# bleumaus-nrf51822-mk-1_0_3.net
KiCad netlist of a schematic drawn in EAGLE
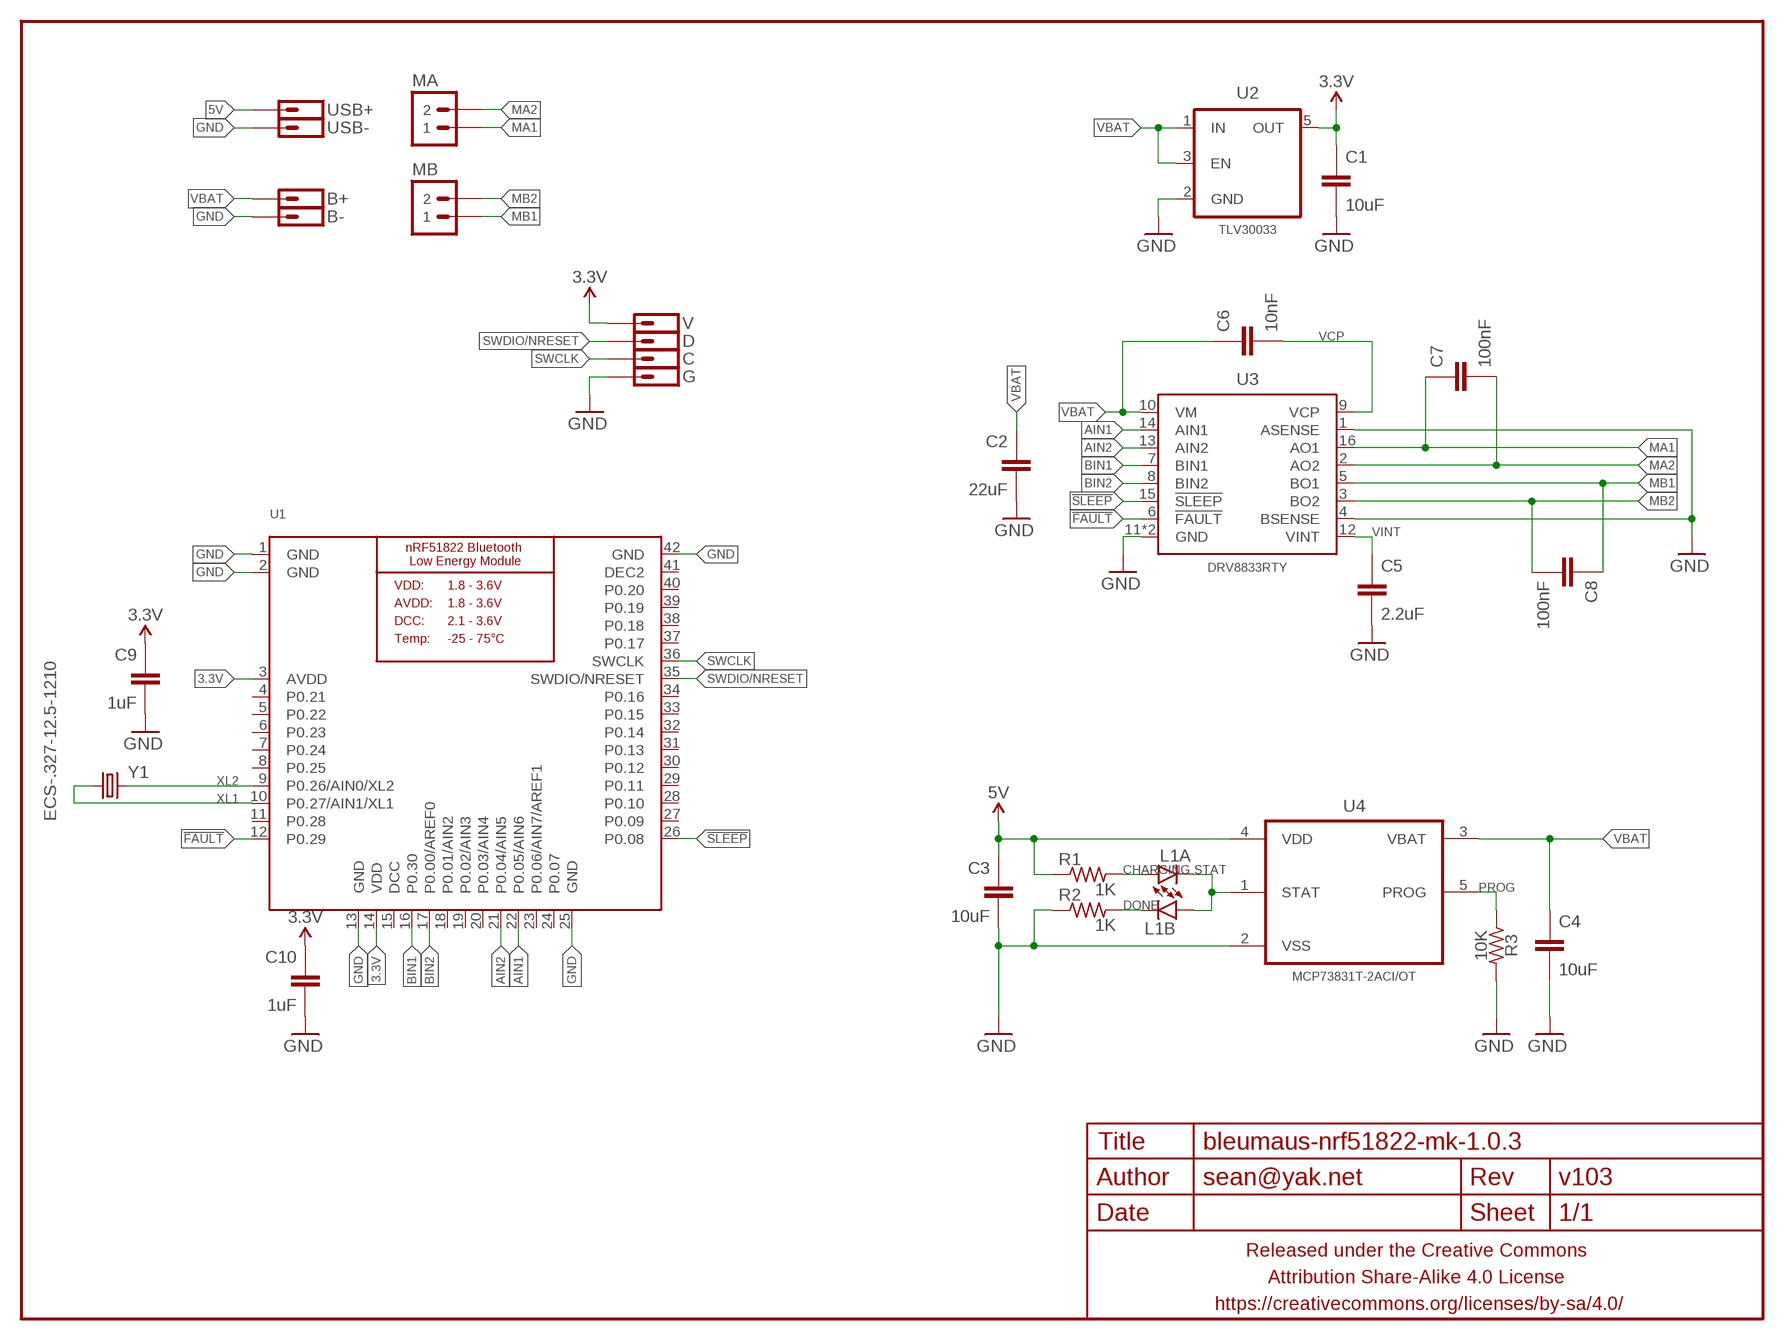
[diagram p0: schematic, sheet 1]

(export (version "E")
  (design (tool "Eeschema 10.0.6"))
  (components
    (comp (ref "B+")
      (value "M01SMD-1DIA")
      (footprint "eagle-import:1X01-SMD-1MM-DIA")
      (libsource (lib "eagle-import") (part "M01SMD-1DIA"))
    )
    (comp (ref "B-")
      (value "M01SMD-1DIA")
      (footprint "eagle-import:1X01-SMD-1MM-DIA")
      (libsource (lib "eagle-import") (part "M01SMD-1DIA"))
    )
    (comp (ref "C")
      (value "M01SMD-1DIA")
      (footprint "eagle-import:1X01-SMD-1MM-DIA")
      (libsource (lib "eagle-import") (part "M01SMD-1DIA"))
    )
    (comp (ref "C1")
      (value "10uF")
      (footprint "eagle-import:C0402")
      (libsource (lib "eagle-import") (part "CAPACITOR-CERAMICC0402"))
    )
    (comp (ref "C2")
      (value "22uF")
      (footprint "eagle-import:C1206")
      (libsource (lib "eagle-import") (part "CAPACITOR-CERAMICC1206"))
    )
    (comp (ref "C3")
      (value "10uF")
      (footprint "eagle-import:C0402")
      (libsource (lib "eagle-import") (part "CAPACITOR-CERAMICC0402"))
    )
    (comp (ref "C4")
      (value "10uF")
      (footprint "eagle-import:C0402")
      (libsource (lib "eagle-import") (part "CAPACITOR-CERAMICC0402"))
    )
    (comp (ref "C5")
      (value "2.2uF")
      (footprint "eagle-import:C0402")
      (libsource (lib "eagle-import") (part "CAPACITOR-CERAMICC0402"))
    )
    (comp (ref "C6")
      (value "10nF")
      (footprint "eagle-import:C0402")
      (libsource (lib "eagle-import") (part "CAPACITOR-CERAMICC0402"))
    )
    (comp (ref "C7")
      (value "100nF")
      (footprint "eagle-import:C0402")
      (libsource (lib "eagle-import") (part "CAPACITOR-CERAMICC0402"))
    )
    (comp (ref "C8")
      (value "100nF")
      (footprint "eagle-import:C0402")
      (libsource (lib "eagle-import") (part "CAPACITOR-CERAMICC0402"))
    )
    (comp (ref "C9")
      (value "1uF")
      (footprint "eagle-import:C0402")
      (libsource (lib "eagle-import") (part "CAPACITOR-CERAMICC0402"))
    )
    (comp (ref "C10")
      (value "1uF")
      (footprint "eagle-import:C0402")
      (libsource (lib "eagle-import") (part "CAPACITOR-CERAMICC0402"))
    )
    (comp (ref "D")
      (value "M01SMD-1DIA")
      (footprint "eagle-import:1X01-SMD-1MM-DIA")
      (libsource (lib "eagle-import") (part "M01SMD-1DIA"))
    )
    (comp (ref "FRAME1")
      (value "FRAME-LETTERNO_PACKAGE")
      (footprint "eagle-import:DUMMY")
      (fields
        (field (name "DESIGNER") "sean@yak.net")
        (field (name "VERSION") "v103")
        (field (name "DESIGNER_1") "sean@yak.net")
        (field (name "VERSION_1") "v103")
      )
      (libsource (lib "eagle-import") (part "FRAME-LETTERNO_PACKAGE"))
    )
    (comp (ref "G")
      (value "M01SMD-1DIA")
      (footprint "eagle-import:1X01-SMD-1MM-DIA")
      (libsource (lib "eagle-import") (part "M01SMD-1DIA"))
    )
    (comp (ref "L1")
      (value "LED-BICOLORSML-P24MUW")
      (footprint "eagle-import:SML-P24MUW")
      (libsource (lib "eagle-import") (part "LED-BICOLORSML-P24MUW"))
    )
    (comp (ref "MA")
      (value "M02PTH-2MM")
      (footprint "eagle-import:1X02-2MM-PTH")
      (libsource (lib "eagle-import") (part "M02PTH-2MM"))
    )
    (comp (ref "MB")
      (value "M02PTH-2MM")
      (footprint "eagle-import:1X02-2MM-PTH")
      (libsource (lib "eagle-import") (part "M02PTH-2MM"))
    )
    (comp (ref "R1")
      (value "1K")
      (footprint "eagle-import:R0402")
      (libsource (lib "eagle-import") (part "RESISTORR0402"))
    )
    (comp (ref "R2")
      (value "1K")
      (footprint "eagle-import:R0402")
      (libsource (lib "eagle-import") (part "RESISTORR0402"))
    )
    (comp (ref "R3")
      (value "10K")
      (footprint "eagle-import:R0402")
      (libsource (lib "eagle-import") (part "RESISTORR0402"))
    )
    (comp (ref "U1")
      (value "NRF51822_MODULE_MDBT40")
      (footprint "eagle-import:BLE_MODULE_RAYTAC_MDBT40")
      (libsource (lib "eagle-import") (part "NRF51822_MODULE_MDBT40"))
    )
    (comp (ref "U2")
      (value "TLV30033")
      (footprint "eagle-import:SC70-TIGHTER")
      (libsource (lib "eagle-import") (part "V_REG_ENTLV700XXDCK-TIGHTER"))
    )
    (comp (ref "U3")
      (value "DRV8833RTY")
      (footprint "eagle-import:PWQFN-16")
      (libsource (lib "eagle-import") (part "DRV8833RTY"))
    )
    (comp (ref "U4")
      (value "MCP73831T-2ACI/OT")
      (footprint "eagle-import:SOT95P280X145-5N")
      (libsource (lib "eagle-import") (part "MCP73831T-2ACI/OT"))
    )
    (comp (ref "USB+")
      (value "M01SMD-1DIA")
      (footprint "eagle-import:1X01-SMD-1MM-DIA")
      (libsource (lib "eagle-import") (part "M01SMD-1DIA"))
    )
    (comp (ref "USB-")
      (value "M01SMD-1DIA")
      (footprint "eagle-import:1X01-SMD-1MM-DIA")
      (libsource (lib "eagle-import") (part "M01SMD-1DIA"))
    )
    (comp (ref "V")
      (value "M01SMD-1DIA")
      (footprint "eagle-import:1X01-SMD-1MM-DIA")
      (libsource (lib "eagle-import") (part "M01SMD-1DIA"))
    )
    (comp (ref "Y1")
      (value "ECS-.327-12.5-1210")
      (footprint "eagle-import:CRYSTAL-1X1.2MM")
      (libsource (lib "eagle-import") (part "CRYSTAL1X1.2MM"))
    )
  )
  (nets
    (net (code "1") (name "/CHARGING") (class "Default")
      (node (ref "L1") (pin "1") (pinfunction "A_1") (pintype "passive"))
      (node (ref "R1") (pin "2") (pinfunction "2_2") (pintype "passive"))
    )
    (net (code "2") (name "/DCC") (class "Default")
      (node (ref "U1") (pin "15") (pinfunction "DCC_15") (pintype "power_in"))
    )
    (net (code "3") (name "/DEC2") (class "Default")
      (node (ref "U1") (pin "41") (pinfunction "DEC2_41") (pintype "power_in"))
    )
    (net (code "4") (name "/DONE") (class "Default")
      (node (ref "L1") (pin "3") (pinfunction "C_3") (pintype "passive"))
      (node (ref "R2") (pin "2") (pinfunction "2_2") (pintype "passive"))
    )
    (net (code "5") (name "/PROG") (class "Default")
      (node (ref "R3") (pin "1") (pinfunction "1_1") (pintype "passive"))
      (node (ref "U4") (pin "5") (pinfunction "PROG_5") (pintype "input"))
    )
    (net (code "6") (name "/STAT") (class "Default")
      (node (ref "L1") (pin "2") (pinfunction "A_2") (pintype "passive"))
      (node (ref "L1") (pin "4") (pinfunction "C_4") (pintype "passive"))
      (node (ref "U4") (pin "1") (pinfunction "STAT_1") (pintype "output"))
    )
    (net (code "7") (name "/VCP") (class "Default")
      (node (ref "C6") (pin "2") (pinfunction "2_2") (pintype "passive"))
      (node (ref "U3") (pin "9") (pinfunction "VCP_9") (pintype "bidirectional"))
    )
    (net (code "8") (name "/VINT") (class "Default")
      (node (ref "C5") (pin "1") (pinfunction "1_1") (pintype "passive"))
      (node (ref "U3") (pin "12") (pinfunction "VINT_12") (pintype "bidirectional"))
    )
    (net (code "9") (name "/XL1") (class "Default")
      (node (ref "U1") (pin "10") (pinfunction "P0.27/AIN1/XL1_10") (pintype "bidirectional"))
      (node (ref "Y1") (pin "1") (pinfunction "1_1") (pintype "passive"))
    )
    (net (code "10") (name "/XL2") (class "Default")
      (node (ref "U1") (pin "9") (pinfunction "P0.26/AIN0/XL2_9") (pintype "bidirectional"))
      (node (ref "Y1") (pin "2") (pinfunction "2_2") (pintype "passive"))
    )
    (net (code "11") (name "/~{FAULT}") (class "Default")
      (node (ref "U1") (pin "12") (pinfunction "P0.29_12") (pintype "bidirectional"))
      (node (ref "U3") (pin "6") (pinfunction "~{FAULT}_6") (pintype "output"))
    )
    (net (code "12") (name "/~{SLEEP}") (class "Default")
      (node (ref "U1") (pin "26") (pinfunction "P0.08_26") (pintype "bidirectional"))
      (node (ref "U3") (pin "15") (pinfunction "~{SLEEP}_15") (pintype "input"))
    )
    (net (code "13") (name "3.3V") (class "Default")
      (node (ref "C1") (pin "1") (pinfunction "1_1") (pintype "passive"))
      (node (ref "C10") (pin "1") (pinfunction "1_1") (pintype "passive"))
      (node (ref "C9") (pin "1") (pinfunction "1_1") (pintype "passive"))
      (node (ref "U1") (pin "14") (pinfunction "VDD_14") (pintype "power_in"))
      (node (ref "U1") (pin "3") (pinfunction "AVDD_3") (pintype "power_in"))
      (node (ref "U2") (pin "5") (pinfunction "OUT_5") (pintype "passive"))
      (node (ref "V") (pin "P$1") (pinfunction "1_P$1") (pintype "passive"))
    )
    (net (code "14") (name "5V") (class "Default")
      (node (ref "C3") (pin "1") (pinfunction "1_1") (pintype "passive"))
      (node (ref "R1") (pin "1") (pinfunction "1_1") (pintype "passive"))
      (node (ref "U4") (pin "4") (pinfunction "VDD_4") (pintype "power_in"))
      (node (ref "USB+") (pin "P$1") (pinfunction "1_P$1") (pintype "passive"))
    )
    (net (code "15") (name "AIN1") (class "Default")
      (node (ref "U1") (pin "22") (pinfunction "P0.05/AIN6_22") (pintype "bidirectional"))
      (node (ref "U3") (pin "14") (pinfunction "AIN1_14") (pintype "input"))
    )
    (net (code "16") (name "AIN2") (class "Default")
      (node (ref "U1") (pin "21") (pinfunction "P0.04/AIN5_21") (pintype "bidirectional"))
      (node (ref "U3") (pin "13") (pinfunction "AIN2_13") (pintype "input"))
    )
    (net (code "17") (name "BIN1") (class "Default")
      (node (ref "U1") (pin "16") (pinfunction "P0.30_16") (pintype "bidirectional"))
      (node (ref "U3") (pin "7") (pinfunction "BIN1_7") (pintype "input"))
    )
    (net (code "18") (name "BIN2") (class "Default")
      (node (ref "U1") (pin "17") (pinfunction "P0.00/AREF0_17") (pintype "bidirectional"))
      (node (ref "U3") (pin "8") (pinfunction "BIN2_8") (pintype "input"))
    )
    (net (code "19") (name "GND") (class "Default")
      (node (ref "B-") (pin "P$1") (pinfunction "1_P$1") (pintype "passive"))
      (node (ref "C1") (pin "2") (pinfunction "2_2") (pintype "passive"))
      (node (ref "C10") (pin "2") (pinfunction "2_2") (pintype "passive"))
      (node (ref "C2") (pin "2") (pinfunction "2_2") (pintype "passive"))
      (node (ref "C3") (pin "2") (pinfunction "2_2") (pintype "passive"))
      (node (ref "C4") (pin "2") (pinfunction "2_2") (pintype "passive"))
      (node (ref "C5") (pin "2") (pinfunction "2_2") (pintype "passive"))
      (node (ref "C9") (pin "2") (pinfunction "2_2") (pintype "passive"))
      (node (ref "G") (pin "P$1") (pinfunction "1_P$1") (pintype "passive"))
      (node (ref "R2") (pin "1") (pinfunction "1_1") (pintype "passive"))
      (node (ref "R3") (pin "2") (pinfunction "2_2") (pintype "passive"))
      (node (ref "U1") (pin "1") (pinfunction "GND_1") (pintype "power_in"))
      (node (ref "U1") (pin "13") (pinfunction "GND_13") (pintype "power_in"))
      (node (ref "U1") (pin "2") (pinfunction "GND_2") (pintype "power_in"))
      (node (ref "U1") (pin "25") (pinfunction "GND_25") (pintype "power_in"))
      (node (ref "U1") (pin "42") (pinfunction "GND_42") (pintype "power_in"))
      (node (ref "U2") (pin "2") (pinfunction "GND_2") (pintype "input"))
      (node (ref "U3") (pin "1") (pinfunction "ASENSE_1") (pintype "bidirectional"))
      (node (ref "U3") (pin "11") (pinfunction "GND_11") (pintype "bidirectional"))
      (node (ref "U3") (pin "17") (pinfunction "GND_17") (pintype "bidirectional"))
      (node (ref "U3") (pin "4") (pinfunction "BSENSE_4") (pintype "bidirectional"))
      (node (ref "U4") (pin "2") (pinfunction "VSS_2") (pintype "power_in"))
      (node (ref "USB-") (pin "P$1") (pinfunction "1_P$1") (pintype "passive"))
    )
    (net (code "20") (name "MA1") (class "Default")
      (node (ref "C7") (pin "1") (pinfunction "1_1") (pintype "passive"))
      (node (ref "MA") (pin "P$1") (pinfunction "1_P$1") (pintype "passive"))
      (node (ref "U3") (pin "16") (pinfunction "AO1_16") (pintype "bidirectional"))
    )
    (net (code "21") (name "MA2") (class "Default")
      (node (ref "C7") (pin "2") (pinfunction "2_2") (pintype "passive"))
      (node (ref "MA") (pin "P$2") (pinfunction "2_P$2") (pintype "passive"))
      (node (ref "U3") (pin "2") (pinfunction "AO2_2") (pintype "bidirectional"))
    )
    (net (code "22") (name "MB1") (class "Default")
      (node (ref "C8") (pin "1") (pinfunction "1_1") (pintype "passive"))
      (node (ref "MB") (pin "P$1") (pinfunction "1_P$1") (pintype "passive"))
      (node (ref "U3") (pin "5") (pinfunction "BO1_5") (pintype "bidirectional"))
    )
    (net (code "23") (name "MB2") (class "Default")
      (node (ref "C8") (pin "2") (pinfunction "2_2") (pintype "passive"))
      (node (ref "MB") (pin "P$2") (pinfunction "2_P$2") (pintype "passive"))
      (node (ref "U3") (pin "3") (pinfunction "BO2_3") (pintype "bidirectional"))
    )
    (net (code "24") (name "SWCLK") (class "Default")
      (node (ref "C") (pin "P$1") (pinfunction "1_P$1") (pintype "passive"))
      (node (ref "U1") (pin "36") (pinfunction "SWCLK_36") (pintype "bidirectional"))
    )
    (net (code "25") (name "SWDIO{slash}NRESET") (class "Default")
      (node (ref "D") (pin "P$1") (pinfunction "1_P$1") (pintype "passive"))
      (node (ref "U1") (pin "35") (pinfunction "SWDIO/NRESET_35") (pintype "bidirectional"))
    )
    (net (code "26") (name "VBAT") (class "Default")
      (node (ref "B+") (pin "P$1") (pinfunction "1_P$1") (pintype "passive"))
      (node (ref "C2") (pin "1") (pinfunction "1_1") (pintype "passive"))
      (node (ref "C4") (pin "1") (pinfunction "1_1") (pintype "passive"))
      (node (ref "C6") (pin "1") (pinfunction "1_1") (pintype "passive"))
      (node (ref "U2") (pin "1") (pinfunction "IN_1") (pintype "input"))
      (node (ref "U2") (pin "3") (pinfunction "EN_3") (pintype "input"))
      (node (ref "U3") (pin "10") (pinfunction "VM_10") (pintype "bidirectional"))
      (node (ref "U4") (pin "3") (pinfunction "VBAT_3") (pintype "output"))
    )
    (net (code "27") (name "unconnected-(U1-P0.01{slash}AIN2-Pad18)") (class "Default")
      (node (ref "U1") (pin "18") (pinfunction "P0.01/AIN2_18") (pintype "bidirectional"))
    )
    (net (code "28") (name "unconnected-(U1-P0.02{slash}AIN3-Pad19)") (class "Default")
      (node (ref "U1") (pin "19") (pinfunction "P0.02/AIN3_19") (pintype "bidirectional"))
    )
    (net (code "29") (name "unconnected-(U1-P0.03{slash}AIN4-Pad20)") (class "Default")
      (node (ref "U1") (pin "20") (pinfunction "P0.03/AIN4_20") (pintype "bidirectional"))
    )
    (net (code "30") (name "unconnected-(U1-P0.06{slash}AIN7{slash}AREF1-Pad23)") (class "Default")
      (node (ref "U1") (pin "23") (pinfunction "P0.06/AIN7/AREF1_23") (pintype "bidirectional"))
    )
    (net (code "31") (name "unconnected-(U1-P0.07-Pad24)") (class "Default")
      (node (ref "U1") (pin "24") (pinfunction "P0.07_24") (pintype "bidirectional"))
    )
    (net (code "32") (name "unconnected-(U1-P0.09-Pad27)") (class "Default")
      (node (ref "U1") (pin "27") (pinfunction "P0.09_27") (pintype "bidirectional"))
    )
    (net (code "33") (name "unconnected-(U1-P0.10-Pad28)") (class "Default")
      (node (ref "U1") (pin "28") (pinfunction "P0.10_28") (pintype "bidirectional"))
    )
    (net (code "34") (name "unconnected-(U1-P0.11-Pad29)") (class "Default")
      (node (ref "U1") (pin "29") (pinfunction "P0.11_29") (pintype "bidirectional"))
    )
    (net (code "35") (name "unconnected-(U1-P0.12-Pad30)") (class "Default")
      (node (ref "U1") (pin "30") (pinfunction "P0.12_30") (pintype "bidirectional"))
    )
    (net (code "36") (name "unconnected-(U1-P0.13-Pad31)") (class "Default")
      (node (ref "U1") (pin "31") (pinfunction "P0.13_31") (pintype "bidirectional"))
    )
    (net (code "37") (name "unconnected-(U1-P0.14-Pad32)") (class "Default")
      (node (ref "U1") (pin "32") (pinfunction "P0.14_32") (pintype "bidirectional"))
    )
    (net (code "38") (name "unconnected-(U1-P0.15-Pad33)") (class "Default")
      (node (ref "U1") (pin "33") (pinfunction "P0.15_33") (pintype "bidirectional"))
    )
    (net (code "39") (name "unconnected-(U1-P0.16-Pad34)") (class "Default")
      (node (ref "U1") (pin "34") (pinfunction "P0.16_34") (pintype "bidirectional"))
    )
    (net (code "40") (name "unconnected-(U1-P0.17-Pad37)") (class "Default")
      (node (ref "U1") (pin "37") (pinfunction "P0.17_37") (pintype "bidirectional"))
    )
    (net (code "41") (name "unconnected-(U1-P0.18-Pad38)") (class "Default")
      (node (ref "U1") (pin "38") (pinfunction "P0.18_38") (pintype "bidirectional"))
    )
    (net (code "42") (name "unconnected-(U1-P0.19-Pad39)") (class "Default")
      (node (ref "U1") (pin "39") (pinfunction "P0.19_39") (pintype "bidirectional"))
    )
    (net (code "43") (name "unconnected-(U1-P0.20-Pad40)") (class "Default")
      (node (ref "U1") (pin "40") (pinfunction "P0.20_40") (pintype "bidirectional"))
    )
    (net (code "44") (name "unconnected-(U1-P0.21-Pad4)") (class "Default")
      (node (ref "U1") (pin "4") (pinfunction "P0.21_4") (pintype "bidirectional"))
    )
    (net (code "45") (name "unconnected-(U1-P0.22-Pad5)") (class "Default")
      (node (ref "U1") (pin "5") (pinfunction "P0.22_5") (pintype "bidirectional"))
    )
    (net (code "46") (name "unconnected-(U1-P0.23-Pad6)") (class "Default")
      (node (ref "U1") (pin "6") (pinfunction "P0.23_6") (pintype "bidirectional"))
    )
    (net (code "47") (name "unconnected-(U1-P0.24-Pad7)") (class "Default")
      (node (ref "U1") (pin "7") (pinfunction "P0.24_7") (pintype "bidirectional"))
    )
    (net (code "48") (name "unconnected-(U1-P0.25-Pad8)") (class "Default")
      (node (ref "U1") (pin "8") (pinfunction "P0.25_8") (pintype "bidirectional"))
    )
    (net (code "49") (name "unconnected-(U1-P0.28-Pad11)") (class "Default")
      (node (ref "U1") (pin "11") (pinfunction "P0.28_11") (pintype "bidirectional"))
    )
  )
)
